# ProProject_STM32F1_TEMP_2024-12-15.net
KiCad netlist of a schematic drawn in EasyEDA Pro
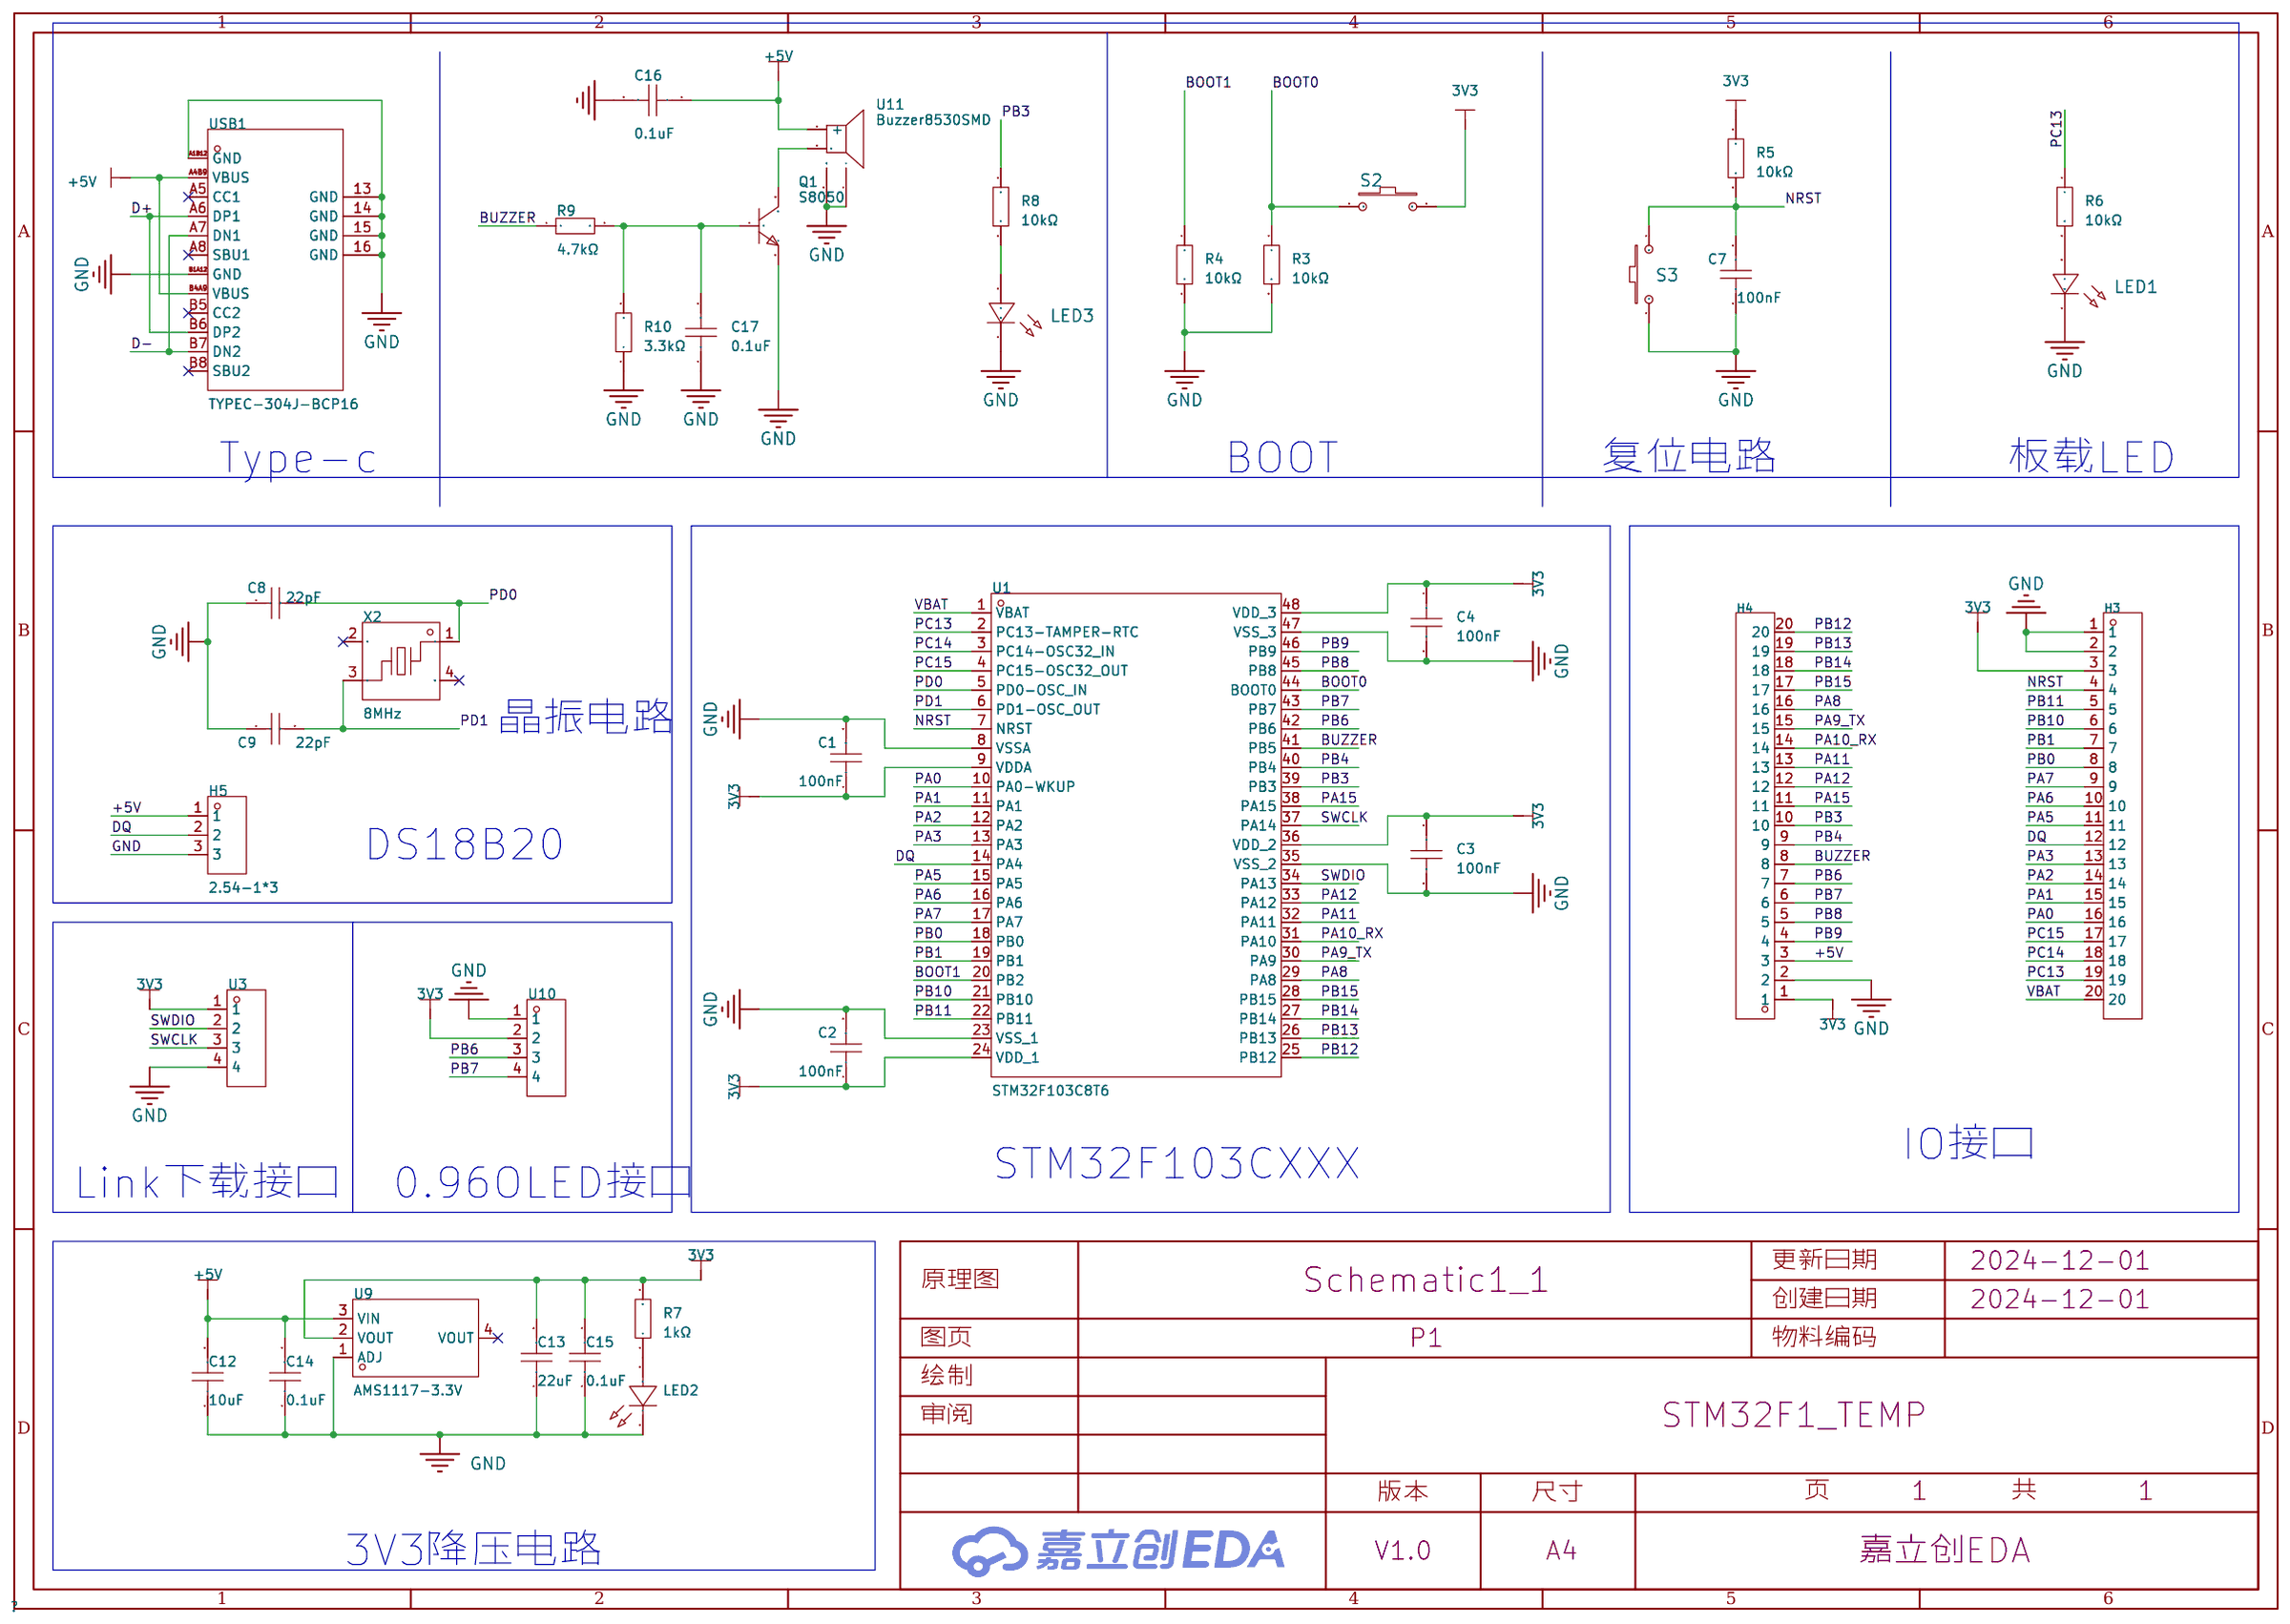
[diagram p0: schematic sheet]

(export (version "E")
  (design (tool "Eeschema 10.0.6"))
  (components
    (comp (ref "C1")
      (value "100nF")
      (footprint "easyedapro:C0603")
      (description "容值:100nF;精度:±10%;额定电压:50V;材质(温度系数):X7R;")
      (fields
        (field (name "Manufacturer Part") "CC0603KRX7R9BB104")
        (field (name "Manufacturer") "YAGEO(国巨)")
      )
      (libsource (lib "easyedapro") (part "CC0603KRX7R9BB104"))
    )
    (comp (ref "C2")
      (value "100nF")
      (footprint "easyedapro:C0603")
      (description "容值:100nF;精度:±10%;额定电压:50V;材质(温度系数):X7R;")
      (fields
        (field (name "Manufacturer Part") "CC0603KRX7R9BB104")
        (field (name "Manufacturer") "YAGEO(国巨)")
      )
      (libsource (lib "easyedapro") (part "CC0603KRX7R9BB104"))
    )
    (comp (ref "C3")
      (value "100nF")
      (footprint "easyedapro:C0603")
      (description "容值:100nF;精度:±10%;额定电压:50V;材质(温度系数):X7R;")
      (fields
        (field (name "Manufacturer Part") "CC0603KRX7R9BB104")
        (field (name "Manufacturer") "YAGEO(国巨)")
      )
      (libsource (lib "easyedapro") (part "CC0603KRX7R9BB104"))
    )
    (comp (ref "C4")
      (value "100nF")
      (footprint "easyedapro:C0603")
      (description "容值:100nF;精度:±10%;额定电压:50V;材质(温度系数):X7R;")
      (fields
        (field (name "Manufacturer Part") "CC0603KRX7R9BB104")
        (field (name "Manufacturer") "YAGEO(国巨)")
      )
      (libsource (lib "easyedapro") (part "CC0603KRX7R9BB104"))
    )
    (comp (ref "C7")
      (value "100nF")
      (footprint "easyedapro:C0603")
      (description "容值:100nF;精度:±10%;额定电压:50V;材质(温度系数):X7R;")
      (fields
        (field (name "Manufacturer Part") "CC0603KRX7R9BB104")
        (field (name "Manufacturer") "YAGEO(国巨)")
      )
      (libsource (lib "easyedapro") (part "CC0603KRX7R9BB104"))
    )
    (comp (ref "C8")
      (value "22pF")
      (footprint "easyedapro:C0603")
      (description "容值:22pF;精度:±5%;额定电压:50V;材质(温度系数):NP0;")
      (fields
        (field (name "Manufacturer Part") "CC0603JRNPO9BN220")
        (field (name "Manufacturer") "YAGEO(国巨)")
      )
      (libsource (lib "easyedapro") (part "CC0603JRNPO9BN220"))
    )
    (comp (ref "C9")
      (value "22pF")
      (footprint "easyedapro:C0603")
      (description "容值:22pF;精度:±5%;额定电压:50V;材质(温度系数):NP0;")
      (fields
        (field (name "Manufacturer Part") "CC0603JRNPO9BN220")
        (field (name "Manufacturer") "YAGEO(国巨)")
      )
      (libsource (lib "easyedapro") (part "CC0603JRNPO9BN220"))
    )
    (comp (ref "C12")
      (value "10uF")
      (footprint "easyedapro:C0603")
      (libsource (lib "easyedapro") (part "CapAcitance"))
    )
    (comp (ref "C13")
      (value "22uF")
      (footprint "easyedapro:C0603")
      (libsource (lib "easyedapro") (part "CapAcitance"))
    )
    (comp (ref "C14")
      (value "0.1uF")
      (footprint "easyedapro:C0603")
      (libsource (lib "easyedapro") (part "CapAcitance"))
    )
    (comp (ref "C15")
      (value "0.1uF")
      (footprint "easyedapro:C0603")
      (libsource (lib "easyedapro") (part "CapAcitance"))
    )
    (comp (ref "C16")
      (value "0.1uF")
      (footprint "easyedapro:C0603")
      (libsource (lib "easyedapro") (part "CapAcitance"))
    )
    (comp (ref "C17")
      (value "0.1uF")
      (footprint "easyedapro:C0603")
      (libsource (lib "easyedapro") (part "CapAcitance"))
    )
    (comp (ref "H3")
      (value "PZ254-1-20-Z-8.5")
      (footprint "easyedapro:HDR-TH_20P-P2.54-V-M")
      (fields (field (name "Manufacturer") "HCTL(华灿天禄)"))
      (libsource (lib "easyedapro") (part "PZ254-1-20-Z-8.5"))
    )
    (comp (ref "H4")
      (value "PZ254-1-20-Z-8.5")
      (footprint "easyedapro:HDR-TH_20P-P2.54-V-M")
      (fields (field (name "Manufacturer") "HCTL(华灿天禄)"))
      (libsource (lib "easyedapro") (part "PZ254-1-20-Z-8.5"))
    )
    (comp (ref "H5")
      (value "2.54-1*3")
      (footprint "easyedapro:HDR-TH_3P-P2.54-V-M-1")
      (description "插针结构:1x3P;间距:2.54mm;排数:单排;总PIN位数:3P;触头镀层:金;")
      (fields (field (name "Manufacturer") "ZHOURI(洲日)"))
      (libsource (lib "easyedapro") (part "2.54-1*3"))
    )
    (comp (ref "LED1")
      (value "~")
      (footprint "easyedapro:LED_0603")
      (libsource (lib "easyedapro") (part "LED_R"))
    )
    (comp (ref "LED2")
      (value "~")
      (footprint "easyedapro:LED0805-RD_BLUE")
      (fields
        (field (name "Manufacturer Part") "RF-BGB170TS-CB-E0")
        (field (name "Manufacturer") "Refond(瑞丰)")
      )
      (libsource (lib "easyedapro") (part "RF-BGB170TS-CB-E0"))
    )
    (comp (ref "LED3")
      (value "~")
      (footprint "easyedapro:LED_0603")
      (libsource (lib "easyedapro") (part "LED_R"))
    )
    (comp (ref "Q1")
      (value "S8050")
      (footprint "easyedapro:SOT-23-3_L2.9-W1.3-P1.90-LS2.4-BR")
      (description "NPN 25V 500mA 120-400 SOT-23")
      (fields (field (name "Manufacturer") "Doeshare(德芯)"))
      (libsource (lib "easyedapro") (part "S8050_C2931719"))
    )
    (comp (ref "R3")
      (value "10kΩ")
      (footprint "easyedapro:R0603")
      (description "电阻类型:厚膜电阻;阻值:10kΩ;精度:±1%;功率:100mW;温度系数:±100ppm/;最大工作电压:75V;工作温度范围:-55~+155;")
      (fields
        (field (name "Manufacturer Part") "0603WAF1002T5E")
        (field (name "Manufacturer") "UNI-ROYAL(厚声)")
      )
      (libsource (lib "easyedapro") (part "0603WAF1002T5E"))
    )
    (comp (ref "R4")
      (value "10kΩ")
      (footprint "easyedapro:R0603")
      (description "电阻类型:厚膜电阻;阻值:10kΩ;精度:±1%;功率:100mW;温度系数:±100ppm/;最大工作电压:75V;工作温度范围:-55~+155;")
      (fields
        (field (name "Manufacturer Part") "0603WAF1002T5E")
        (field (name "Manufacturer") "UNI-ROYAL(厚声)")
      )
      (libsource (lib "easyedapro") (part "0603WAF1002T5E"))
    )
    (comp (ref "R5")
      (value "10kΩ")
      (footprint "easyedapro:R0603")
      (description "电阻类型:厚膜电阻;阻值:10kΩ;精度:±1%;功率:100mW;温度系数:±100ppm/;最大工作电压:75V;工作温度范围:-55~+155;")
      (fields
        (field (name "Manufacturer Part") "0603WAF1002T5E")
        (field (name "Manufacturer") "UNI-ROYAL(厚声)")
      )
      (libsource (lib "easyedapro") (part "0603WAF1002T5E"))
    )
    (comp (ref "R6")
      (value "10kΩ")
      (footprint "easyedapro:R0603")
      (description "电阻类型:厚膜电阻;阻值:10kΩ;精度:±1%;功率:100mW;温度系数:±100ppm/;最大工作电压:75V;工作温度范围:-55~+155;")
      (fields
        (field (name "Manufacturer Part") "0603WAF1002T5E")
        (field (name "Manufacturer") "UNI-ROYAL(厚声)")
      )
      (libsource (lib "easyedapro") (part "0603WAF1002T5E"))
    )
    (comp (ref "R7")
      (value "1kΩ")
      (footprint "easyedapro:R0805")
      (description "阻值:1kΩ;精度:±5%;功率:125mW;温度系数:±100ppm/;最大工作电压:150V;工作温度范围:-55~+155;")
      (fields (field (name "Manufacturer Part") "RS-05K102JT") (field (name "Manufacturer") "FH(风华)"))
      (libsource (lib "easyedapro") (part "RS-05K102JT"))
    )
    (comp (ref "R8")
      (value "10kΩ")
      (footprint "easyedapro:R0603")
      (description "电阻类型:厚膜电阻;阻值:10kΩ;精度:±1%;功率:100mW;温度系数:±100ppm/;最大工作电压:75V;工作温度范围:-55~+155;")
      (fields
        (field (name "Manufacturer Part") "0603WAF1002T5E")
        (field (name "Manufacturer") "UNI-ROYAL(厚声)")
      )
      (libsource (lib "easyedapro") (part "0603WAF1002T5E"))
    )
    (comp (ref "R9")
      (value "4.7kΩ")
      (footprint "easyedapro:R0603")
      (description "电阻类型:厚膜电阻;阻值:4.7kΩ;精度:±1%;功率:100mW;最大工作电压:50V;温度系数:±100ppm/°C;")
      (fields (field (name "Manufacturer Part") "AECR0603F4K70K9") (field (name "Manufacturer") "RESI(开步睿思)"))
      (libsource (lib "easyedapro") (part "AECR0603F4K70K9"))
    )
    (comp (ref "R10")
      (value "3.3kΩ")
      (footprint "easyedapro:R0603")
      (description "电阻类型:厚膜电阻;阻值:3.3kΩ;精度:±1%;功率:100mW;最大工作电压:75V;温度系数:±100ppm/°C;")
      (fields
        (field (name "Manufacturer Part") "0603WAF3301T5E")
        (field (name "Manufacturer") "UNI-ROYAL(厚声)")
      )
      (libsource (lib "easyedapro") (part "0603WAF3301T5E"))
    )
    (comp (ref "S2")
      (value "按键-2Pin")
      (footprint "easyedapro:BUTTON_ALPS")
      (description "--Ƭ")
      (fields (field (name "Publisher") "Altium Limited"))
      (libsource (lib "easyedapro") (part "-2Pin"))
    )
    (comp (ref "S3")
      (value "按键-2Pin")
      (footprint "easyedapro:BUTTON_ALPS")
      (description "--Ƭ")
      (fields (field (name "Publisher") "Altium Limited"))
      (libsource (lib "easyedapro") (part "-2Pin"))
    )
    (comp (ref "U1")
      (value "STM32F103C8T6")
      (footprint "easyedapro:LQFP-48_L7.0-W7.0-P0.50-LS9.0-BL")
      (description "CPU内核:ARM-M3;程序存储容量:64KB;RAM总容量:20KB;GPIO端口数量:37;工作电压范围:2V~3.6V;CPU最大主频:72MHz;程序存储器类型:FLASH;")
      (fields (field (name "Manufacturer") "ST(意法半导体)"))
      (libsource (lib "easyedapro") (part "STM32F103C8T6"))
    )
    (comp (ref "U3")
      (value "XDZ254-1-04-Z-2.5-G1")
      (footprint "easyedapro:HDR-TH_4P-P2.54-V-M")
      (fields (field (name "Manufacturer") "XUNDA(讯答)"))
      (libsource (lib "easyedapro") (part "XDZ254-1-04-Z-2.5-G1"))
    )
    (comp (ref "U9")
      (value "AMS1117-3.3V")
      (footprint "easyedapro:SOT-223-4_L6.5-W3.5-P2.30-LS7.0-BR")
      (fields (field (name "Manufacturer") "TI(德州仪器)"))
      (libsource (lib "easyedapro") (part "REG1117A"))
    )
    (comp (ref "U10")
      (value "XDZ254-1-04-Z-2.5-G1")
      (footprint "easyedapro:HDR-TH_4P-P2.54-V-M")
      (fields (field (name "Manufacturer") "XUNDA(讯答)"))
      (libsource (lib "easyedapro") (part "XDZ254-1-04-Z-2.5-G1"))
    )
    (comp (ref "U11")
      (value "Buzzer8530SMD")
      (footprint "easyedapro:BUZ-SMD_4P-L8.5-W8.5-P8.50-TL")
      (libsource (lib "easyedapro") (part "BUZZER8530SMD"))
    )
    (comp (ref "USB1")
      (value "TYPEC-304J-BCP16")
      (footprint "easyedapro:USB-C-SMD_TYPEC-304J-BCP16")
      (fields (field (name "Manufacturer") "XUNPU(讯普)"))
      (libsource (lib "easyedapro") (part "TYPEC-304J-BCP16"))
    )
    (comp (ref "X2")
      (value "8MHz")
      (footprint "easyedapro:CRYSTAL-SMD_4P-L3.2-W2.5-BL")
      (description "晶振类型:贴片晶振;频率:8MHz;常温频差:±10ppm;外接负载电容:20pF;频率稳定度(全温):±20ppm;")
      (fields (field (name "Manufacturer Part") "X32258MSB4SI") (field (name "Manufacturer") "YXC(扬兴晶振)"))
      (libsource (lib "easyedapro") (part "X32258MSB4SI"))
    )
  )
  (nets
    (net (code "1") (name "+5V") (class "Default")
      (node (ref "C12") (pin "2") (pinfunction "2_2") (pintype "input"))
      (node (ref "C14") (pin "2") (pinfunction "2_2") (pintype "input"))
      (node (ref "C16") (pin "1") (pinfunction "1_1") (pintype "input"))
      (node (ref "H4") (pin "3") (pinfunction "3_3") (pintype "input"))
      (node (ref "H5") (pin "1") (pinfunction "1_1") (pintype "unspecified"))
      (node (ref "U11") (pin "1") (pinfunction "+_1") (pintype "unspecified"))
      (node (ref "U9") (pin "3") (pinfunction "VIN_3") (pintype "input"))
      (node (ref "USB1") (pin "A4B9") (pinfunction "VBUS_A4B9") (pintype "unspecified"))
      (node (ref "USB1") (pin "B4A9") (pinfunction "VBUS_B4A9") (pintype "unspecified"))
    )
    (net (code "2") (name "/BOOT0") (class "Default")
      (node (ref "R3") (pin "1") (pinfunction "1_1") (pintype "input"))
      (node (ref "S2") (pin "1") (pinfunction "1_1") (pintype "input"))
      (node (ref "U1") (pin "44") (pinfunction "BOOT0_44") (pintype "unspecified"))
    )
    (net (code "3") (name "/BOOT1") (class "Default")
      (node (ref "R4") (pin "1") (pinfunction "1_1") (pintype "input"))
      (node (ref "U1") (pin "20") (pinfunction "PB2_20") (pintype "unspecified"))
    )
    (net (code "4") (name "/BUZZER") (class "Default")
      (node (ref "H4") (pin "8") (pinfunction "8_8") (pintype "input"))
      (node (ref "R9") (pin "1") (pinfunction "1_1") (pintype "unspecified"))
      (node (ref "U1") (pin "41") (pinfunction "PB5_41") (pintype "unspecified"))
    )
    (net (code "5") (name "/D+") (class "Default")
      (node (ref "USB1") (pin "A6") (pinfunction "DP1_A6") (pintype "unspecified"))
      (node (ref "USB1") (pin "B6") (pinfunction "DP2_B6") (pintype "unspecified"))
    )
    (net (code "6") (name "/D-") (class "Default")
      (node (ref "USB1") (pin "A7") (pinfunction "DN1_A7") (pintype "unspecified"))
      (node (ref "USB1") (pin "B7") (pinfunction "DN2_B7") (pintype "unspecified"))
    )
    (net (code "7") (name "/DQ") (class "Default")
      (node (ref "H3") (pin "12") (pinfunction "12_12") (pintype "input"))
      (node (ref "H5") (pin "2") (pinfunction "2_2") (pintype "unspecified"))
      (node (ref "U1") (pin "14") (pinfunction "PA4_14") (pintype "unspecified"))
    )
    (net (code "8") (name "/NRST") (class "Default")
      (node (ref "C7") (pin "2") (pinfunction "2_2") (pintype "unspecified"))
      (node (ref "H3") (pin "4") (pinfunction "4_4") (pintype "input"))
      (node (ref "R5") (pin "2") (pinfunction "2_2") (pintype "input"))
      (node (ref "S3") (pin "2") (pinfunction "2_2") (pintype "input"))
      (node (ref "U1") (pin "7") (pinfunction "NRST_7") (pintype "unspecified"))
    )
    (net (code "9") (name "/PA0") (class "Default")
      (node (ref "H3") (pin "16") (pinfunction "16_16") (pintype "input"))
      (node (ref "U1") (pin "10") (pinfunction "PA0-WKUP_10") (pintype "unspecified"))
    )
    (net (code "10") (name "/PA1") (class "Default")
      (node (ref "H3") (pin "15") (pinfunction "15_15") (pintype "input"))
      (node (ref "U1") (pin "11") (pinfunction "PA1_11") (pintype "unspecified"))
    )
    (net (code "11") (name "/PA2") (class "Default")
      (node (ref "H3") (pin "14") (pinfunction "14_14") (pintype "input"))
      (node (ref "U1") (pin "12") (pinfunction "PA2_12") (pintype "unspecified"))
    )
    (net (code "12") (name "/PA3") (class "Default")
      (node (ref "H3") (pin "13") (pinfunction "13_13") (pintype "input"))
      (node (ref "U1") (pin "13") (pinfunction "PA3_13") (pintype "unspecified"))
    )
    (net (code "13") (name "/PA5") (class "Default")
      (node (ref "H3") (pin "11") (pinfunction "11_11") (pintype "input"))
      (node (ref "U1") (pin "15") (pinfunction "PA5_15") (pintype "unspecified"))
    )
    (net (code "14") (name "/PA6") (class "Default")
      (node (ref "H3") (pin "10") (pinfunction "10_10") (pintype "input"))
      (node (ref "U1") (pin "16") (pinfunction "PA6_16") (pintype "unspecified"))
    )
    (net (code "15") (name "/PA7") (class "Default")
      (node (ref "H3") (pin "9") (pinfunction "9_9") (pintype "input"))
      (node (ref "U1") (pin "17") (pinfunction "PA7_17") (pintype "unspecified"))
    )
    (net (code "16") (name "/PA8") (class "Default")
      (node (ref "H4") (pin "16") (pinfunction "16_16") (pintype "input"))
      (node (ref "U1") (pin "29") (pinfunction "PA8_29") (pintype "unspecified"))
    )
    (net (code "17") (name "/PA9_TX") (class "Default")
      (node (ref "H4") (pin "15") (pinfunction "15_15") (pintype "input"))
      (node (ref "U1") (pin "30") (pinfunction "PA9_30") (pintype "unspecified"))
    )
    (net (code "18") (name "/PA10_RX") (class "Default")
      (node (ref "H4") (pin "14") (pinfunction "14_14") (pintype "input"))
      (node (ref "U1") (pin "31") (pinfunction "PA10_31") (pintype "unspecified"))
    )
    (net (code "19") (name "/PA11") (class "Default")
      (node (ref "H4") (pin "13") (pinfunction "13_13") (pintype "input"))
      (node (ref "U1") (pin "32") (pinfunction "PA11_32") (pintype "unspecified"))
    )
    (net (code "20") (name "/PA12") (class "Default")
      (node (ref "H4") (pin "12") (pinfunction "12_12") (pintype "input"))
      (node (ref "U1") (pin "33") (pinfunction "PA12_33") (pintype "unspecified"))
    )
    (net (code "21") (name "/PA15") (class "Default")
      (node (ref "H4") (pin "11") (pinfunction "11_11") (pintype "input"))
      (node (ref "U1") (pin "38") (pinfunction "PA15_38") (pintype "unspecified"))
    )
    (net (code "22") (name "/PB0") (class "Default")
      (node (ref "H3") (pin "8") (pinfunction "8_8") (pintype "input"))
      (node (ref "U1") (pin "18") (pinfunction "PB0_18") (pintype "unspecified"))
    )
    (net (code "23") (name "/PB1") (class "Default")
      (node (ref "H3") (pin "7") (pinfunction "7_7") (pintype "input"))
      (node (ref "U1") (pin "19") (pinfunction "PB1_19") (pintype "unspecified"))
    )
    (net (code "24") (name "/PB3") (class "Default")
      (node (ref "H4") (pin "10") (pinfunction "10_10") (pintype "input"))
      (node (ref "R8") (pin "1") (pinfunction "1_1") (pintype "input"))
      (node (ref "U1") (pin "39") (pinfunction "PB3_39") (pintype "unspecified"))
    )
    (net (code "25") (name "/PB4") (class "Default")
      (node (ref "H4") (pin "9") (pinfunction "9_9") (pintype "input"))
      (node (ref "U1") (pin "40") (pinfunction "PB4_40") (pintype "unspecified"))
    )
    (net (code "26") (name "/PB6") (class "Default")
      (node (ref "H4") (pin "7") (pinfunction "7_7") (pintype "input"))
      (node (ref "U1") (pin "42") (pinfunction "PB6_42") (pintype "unspecified"))
      (node (ref "U10") (pin "3") (pinfunction "3_3") (pintype "unspecified"))
    )
    (net (code "27") (name "/PB7") (class "Default")
      (node (ref "H4") (pin "6") (pinfunction "6_6") (pintype "input"))
      (node (ref "U1") (pin "43") (pinfunction "PB7_43") (pintype "unspecified"))
      (node (ref "U10") (pin "4") (pinfunction "4_4") (pintype "unspecified"))
    )
    (net (code "28") (name "/PB8") (class "Default")
      (node (ref "H4") (pin "5") (pinfunction "5_5") (pintype "input"))
      (node (ref "U1") (pin "45") (pinfunction "PB8_45") (pintype "unspecified"))
    )
    (net (code "29") (name "/PB9") (class "Default")
      (node (ref "H4") (pin "4") (pinfunction "4_4") (pintype "input"))
      (node (ref "U1") (pin "46") (pinfunction "PB9_46") (pintype "unspecified"))
    )
    (net (code "30") (name "/PB10") (class "Default")
      (node (ref "H3") (pin "6") (pinfunction "6_6") (pintype "input"))
      (node (ref "U1") (pin "21") (pinfunction "PB10_21") (pintype "unspecified"))
    )
    (net (code "31") (name "/PB11") (class "Default")
      (node (ref "H3") (pin "5") (pinfunction "5_5") (pintype "input"))
      (node (ref "U1") (pin "22") (pinfunction "PB11_22") (pintype "unspecified"))
    )
    (net (code "32") (name "/PB12") (class "Default")
      (node (ref "H4") (pin "20") (pinfunction "20_20") (pintype "input"))
      (node (ref "U1") (pin "25") (pinfunction "PB12_25") (pintype "unspecified"))
    )
    (net (code "33") (name "/PB13") (class "Default")
      (node (ref "H4") (pin "19") (pinfunction "19_19") (pintype "input"))
      (node (ref "U1") (pin "26") (pinfunction "PB13_26") (pintype "unspecified"))
    )
    (net (code "34") (name "/PB14") (class "Default")
      (node (ref "H4") (pin "18") (pinfunction "18_18") (pintype "input"))
      (node (ref "U1") (pin "27") (pinfunction "PB14_27") (pintype "unspecified"))
    )
    (net (code "35") (name "/PB15") (class "Default")
      (node (ref "H4") (pin "17") (pinfunction "17_17") (pintype "input"))
      (node (ref "U1") (pin "28") (pinfunction "PB15_28") (pintype "unspecified"))
    )
    (net (code "36") (name "/PC13") (class "Default")
      (node (ref "H3") (pin "19") (pinfunction "19_19") (pintype "input"))
      (node (ref "R6") (pin "1") (pinfunction "1_1") (pintype "input"))
      (node (ref "U1") (pin "2") (pinfunction "PC13-TAMPER-RTC_2") (pintype "unspecified"))
    )
    (net (code "37") (name "/PC14") (class "Default")
      (node (ref "H3") (pin "18") (pinfunction "18_18") (pintype "input"))
      (node (ref "U1") (pin "3") (pinfunction "PC14-OSC32_IN_3") (pintype "unspecified"))
    )
    (net (code "38") (name "/PC15") (class "Default")
      (node (ref "H3") (pin "17") (pinfunction "17_17") (pintype "input"))
      (node (ref "U1") (pin "4") (pinfunction "PC15-OSC32_OUT_4") (pintype "unspecified"))
    )
    (net (code "39") (name "/PD0") (class "Default")
      (node (ref "C8") (pin "2") (pinfunction "2_2") (pintype "input"))
      (node (ref "U1") (pin "5") (pinfunction "PD0-OSC_IN_5") (pintype "unspecified"))
      (node (ref "X2") (pin "1") (pinfunction "1_1") (pintype "input"))
    )
    (net (code "40") (name "/PD1") (class "Default")
      (node (ref "C9") (pin "2") (pinfunction "2_2") (pintype "input"))
      (node (ref "U1") (pin "6") (pinfunction "PD1-OSC_OUT_6") (pintype "unspecified"))
      (node (ref "X2") (pin "3") (pinfunction "3_3") (pintype "input"))
    )
    (net (code "41") (name "/SWCLK") (class "Default")
      (node (ref "U1") (pin "37") (pinfunction "PA14_37") (pintype "unspecified"))
      (node (ref "U3") (pin "3") (pinfunction "3_3") (pintype "unspecified"))
    )
    (net (code "42") (name "/SWDIO") (class "Default")
      (node (ref "U1") (pin "34") (pinfunction "PA13_34") (pintype "unspecified"))
      (node (ref "U3") (pin "2") (pinfunction "2_2") (pintype "unspecified"))
    )
    (net (code "43") (name "/VBAT") (class "Default")
      (node (ref "H3") (pin "20") (pinfunction "20_20") (pintype "input"))
      (node (ref "U1") (pin "1") (pinfunction "VBAT_1") (pintype "unspecified"))
    )
    (net (code "44") (name "3V3") (class "Default")
      (node (ref "C1") (pin "1") (pinfunction "1_1") (pintype "unspecified"))
      (node (ref "C13") (pin "2") (pinfunction "2_2") (pintype "input"))
      (node (ref "C15") (pin "2") (pinfunction "2_2") (pintype "input"))
      (node (ref "C2") (pin "1") (pinfunction "1_1") (pintype "unspecified"))
      (node (ref "C3") (pin "1") (pinfunction "1_1") (pintype "unspecified"))
      (node (ref "C4") (pin "1") (pinfunction "1_1") (pintype "unspecified"))
      (node (ref "H3") (pin "3") (pinfunction "3_3") (pintype "input"))
      (node (ref "H4") (pin "1") (pinfunction "1_1") (pintype "input"))
      (node (ref "R5") (pin "1") (pinfunction "1_1") (pintype "input"))
      (node (ref "R7") (pin "2") (pinfunction "2_2") (pintype "input"))
      (node (ref "S2") (pin "2") (pinfunction "2_2") (pintype "input"))
      (node (ref "U1") (pin "24") (pinfunction "VDD_1_24") (pintype "unspecified"))
      (node (ref "U1") (pin "36") (pinfunction "VDD_2_36") (pintype "unspecified"))
      (node (ref "U1") (pin "48") (pinfunction "VDD_3_48") (pintype "unspecified"))
      (node (ref "U1") (pin "9") (pinfunction "VDDA_9") (pintype "unspecified"))
      (node (ref "U10") (pin "2") (pinfunction "2_2") (pintype "unspecified"))
      (node (ref "U3") (pin "1") (pinfunction "1_1") (pintype "unspecified"))
      (node (ref "U9") (pin "2") (pinfunction "VOUT_2") (pintype "input"))
    )
    (net (code "45") (name "GND") (class "Default")
      (node (ref "C1") (pin "2") (pinfunction "2_2") (pintype "unspecified"))
      (node (ref "C12") (pin "1") (pinfunction "1_1") (pintype "input"))
      (node (ref "C13") (pin "1") (pinfunction "1_1") (pintype "input"))
      (node (ref "C14") (pin "1") (pinfunction "1_1") (pintype "input"))
      (node (ref "C15") (pin "1") (pinfunction "1_1") (pintype "input"))
      (node (ref "C16") (pin "2") (pinfunction "2_2") (pintype "input"))
      (node (ref "C17") (pin "1") (pinfunction "1_1") (pintype "input"))
      (node (ref "C2") (pin "2") (pinfunction "2_2") (pintype "unspecified"))
      (node (ref "C3") (pin "2") (pinfunction "2_2") (pintype "unspecified"))
      (node (ref "C4") (pin "2") (pinfunction "2_2") (pintype "unspecified"))
      (node (ref "C7") (pin "1") (pinfunction "1_1") (pintype "unspecified"))
      (node (ref "C8") (pin "1") (pinfunction "1_1") (pintype "input"))
      (node (ref "C9") (pin "1") (pinfunction "1_1") (pintype "input"))
      (node (ref "H3") (pin "1") (pinfunction "1_1") (pintype "input"))
      (node (ref "H3") (pin "2") (pinfunction "2_2") (pintype "input"))
      (node (ref "H4") (pin "2") (pinfunction "2_2") (pintype "input"))
      (node (ref "H5") (pin "3") (pinfunction "3_3") (pintype "unspecified"))
      (node (ref "LED1") (pin "1") (pinfunction "C_1") (pintype "input"))
      (node (ref "LED2") (pin "1") (pinfunction "K_1") (pintype "input"))
      (node (ref "LED3") (pin "1") (pinfunction "C_1") (pintype "input"))
      (node (ref "Q1") (pin "2") (pinfunction "E_2") (pintype "input"))
      (node (ref "R10") (pin "1") (pinfunction "1_1") (pintype "input"))
      (node (ref "R3") (pin "2") (pinfunction "2_2") (pintype "input"))
      (node (ref "R4") (pin "2") (pinfunction "2_2") (pintype "input"))
      (node (ref "S3") (pin "1") (pinfunction "1_1") (pintype "input"))
      (node (ref "U1") (pin "23") (pinfunction "VSS_1_23") (pintype "unspecified"))
      (node (ref "U1") (pin "35") (pinfunction "VSS_2_35") (pintype "unspecified"))
      (node (ref "U1") (pin "47") (pinfunction "VSS_3_47") (pintype "unspecified"))
      (node (ref "U1") (pin "8") (pinfunction "VSSA_8") (pintype "unspecified"))
      (node (ref "U10") (pin "1") (pinfunction "1_1") (pintype "unspecified"))
      (node (ref "U11") (pin "3") (pinfunction "3_3") (pintype "unspecified"))
      (node (ref "U11") (pin "4") (pinfunction "4_4") (pintype "unspecified"))
      (node (ref "U3") (pin "4") (pinfunction "4_4") (pintype "unspecified"))
      (node (ref "U9") (pin "1") (pinfunction "ADJ_1") (pintype "input"))
      (node (ref "USB1") (pin "13") (pinfunction "GND_13") (pintype "unspecified"))
      (node (ref "USB1") (pin "14") (pinfunction "GND_14") (pintype "unspecified"))
      (node (ref "USB1") (pin "15") (pinfunction "GND_15") (pintype "unspecified"))
      (node (ref "USB1") (pin "16") (pinfunction "GND_16") (pintype "unspecified"))
      (node (ref "USB1") (pin "A1B12") (pinfunction "GND_A1B12") (pintype "unspecified"))
      (node (ref "USB1") (pin "B1A12") (pinfunction "GND_B1A12") (pintype "unspecified"))
    )
    (net (code "46") (name "Net-(LED1-A)") (class "Default")
      (node (ref "LED1") (pin "2") (pinfunction "A_2") (pintype "input"))
      (node (ref "R6") (pin "2") (pinfunction "2_2") (pintype "input"))
    )
    (net (code "47") (name "Net-(LED2-A)") (class "Default")
      (node (ref "LED2") (pin "2") (pinfunction "A_2") (pintype "input"))
      (node (ref "R7") (pin "1") (pinfunction "1_1") (pintype "input"))
    )
    (net (code "48") (name "Net-(LED3-A)") (class "Default")
      (node (ref "LED3") (pin "2") (pinfunction "A_2") (pintype "input"))
      (node (ref "R8") (pin "2") (pinfunction "2_2") (pintype "input"))
    )
    (net (code "49") (name "Net-(Q1-B)") (class "Default")
      (node (ref "C17") (pin "2") (pinfunction "2_2") (pintype "input"))
      (node (ref "Q1") (pin "1") (pinfunction "B_1") (pintype "input"))
      (node (ref "R10") (pin "2") (pinfunction "2_2") (pintype "input"))
      (node (ref "R9") (pin "2") (pinfunction "2_2") (pintype "unspecified"))
    )
    (net (code "50") (name "Net-(Q1-C)") (class "Default")
      (node (ref "Q1") (pin "3") (pinfunction "C_3") (pintype "input"))
      (node (ref "U11") (pin "2") (pinfunction "2_2") (pintype "unspecified"))
    )
    (net (code "51") (name "unconnected-(U9-VOUT-Pad4)") (class "Default")
      (node (ref "U9") (pin "4") (pinfunction "VOUT_4") (pintype "input+no_connect"))
    )
    (net (code "52") (name "unconnected-(USB1-CC1-PadA5)") (class "Default")
      (node (ref "USB1") (pin "A5") (pinfunction "CC1_A5") (pintype "unspecified+no_connect"))
    )
    (net (code "53") (name "unconnected-(USB1-CC2-PadB5)") (class "Default")
      (node (ref "USB1") (pin "B5") (pinfunction "CC2_B5") (pintype "unspecified+no_connect"))
    )
    (net (code "54") (name "unconnected-(USB1-SBU1-PadA8)") (class "Default")
      (node (ref "USB1") (pin "A8") (pinfunction "SBU1_A8") (pintype "unspecified+no_connect"))
    )
    (net (code "55") (name "unconnected-(USB1-SBU2-PadB8)") (class "Default")
      (node (ref "USB1") (pin "B8") (pinfunction "SBU2_B8") (pintype "unspecified+no_connect"))
    )
    (net (code "56") (name "unconnected-(X2-GND-Pad2)") (class "Default")
      (node (ref "X2") (pin "2") (pinfunction "GND_2") (pintype "input+no_connect"))
    )
    (net (code "57") (name "unconnected-(X2-GND-Pad4)") (class "Default")
      (node (ref "X2") (pin "4") (pinfunction "GND_4") (pintype "input+no_connect"))
    )
  )
)
